# Rapide64a.net
KiCad netlist of a schematic drawn in EAGLE
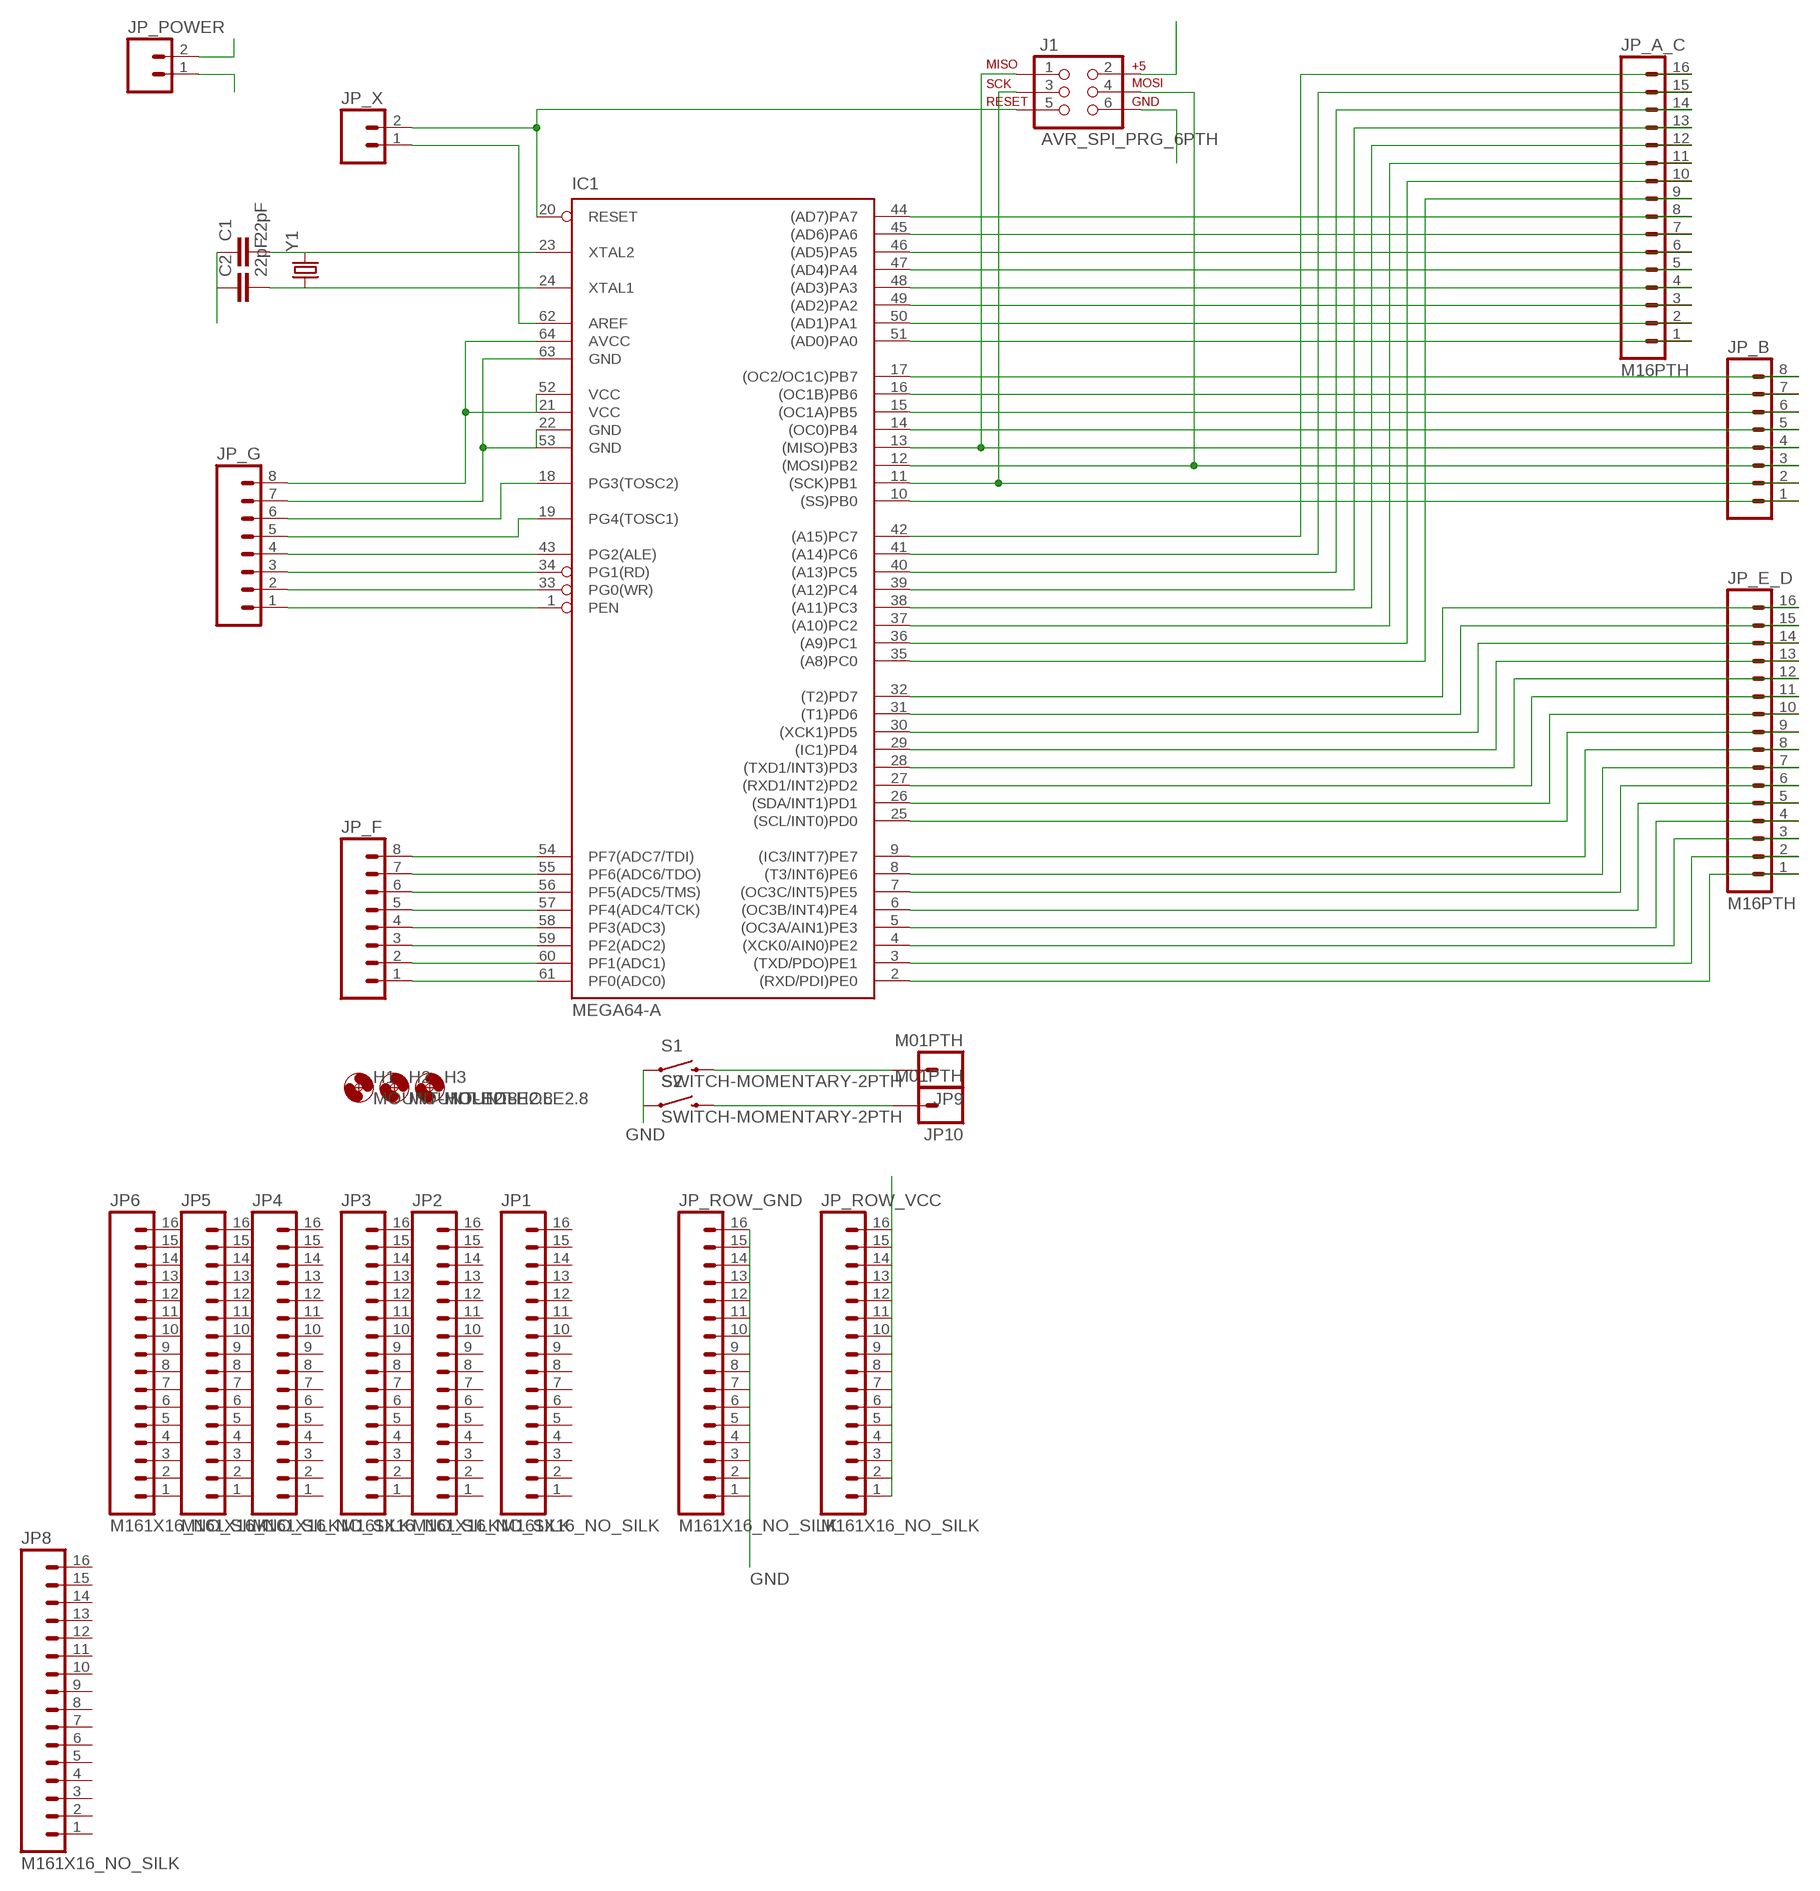
[diagram p0: schematic, sheet 1]

(export (version "E")
  (design (tool "Eeschema 10.0.6"))
  (components
    (comp (ref "C1")
      (value "22pF")
      (footprint "eagle-import:C025-024X044")
      (libsource (lib "eagle-import") (part "C-EU025-024X044"))
    )
    (comp (ref "C2")
      (value "22pF")
      (footprint "eagle-import:C025-024X044")
      (libsource (lib "eagle-import") (part "C-EU025-024X044"))
    )
    (comp (ref "H1")
      (value "MOUNT-HOLE2.8")
      (footprint "eagle-import:2,8")
      (libsource (lib "eagle-import") (part "MOUNT-HOLE2.8"))
    )
    (comp (ref "H2")
      (value "MOUNT-HOLE2.8")
      (footprint "eagle-import:2,8")
      (libsource (lib "eagle-import") (part "MOUNT-HOLE2.8"))
    )
    (comp (ref "H3")
      (value "MOUNT-HOLE2.8")
      (footprint "eagle-import:2,8")
      (libsource (lib "eagle-import") (part "MOUNT-HOLE2.8"))
    )
    (comp (ref "IC1")
      (value "MEGA64-A")
      (footprint "eagle-import:TQFP64")
      (fields (field (name "MPN") "ATMEGA64-16AU"))
      (libsource (lib "eagle-import") (part "MEGA64-A"))
    )
    (comp (ref "J1")
      (value "AVR_SPI_PRG_6PTH")
      (footprint "eagle-import:2X3")
      (libsource (lib "eagle-import") (part "AVR_SPI_PRG_6PTH"))
    )
    (comp (ref "JP1")
      (value "M161X16_NO_SILK")
      (footprint "eagle-import:1X16_NO_SILK")
      (libsource (lib "eagle-import") (part "M161X16_NO_SILK"))
    )
    (comp (ref "JP2")
      (value "M161X16_NO_SILK")
      (footprint "eagle-import:1X16_NO_SILK")
      (libsource (lib "eagle-import") (part "M161X16_NO_SILK"))
    )
    (comp (ref "JP3")
      (value "M161X16_NO_SILK")
      (footprint "eagle-import:1X16_NO_SILK")
      (libsource (lib "eagle-import") (part "M161X16_NO_SILK"))
    )
    (comp (ref "JP4")
      (value "M161X16_NO_SILK")
      (footprint "eagle-import:1X16_NO_SILK")
      (libsource (lib "eagle-import") (part "M161X16_NO_SILK"))
    )
    (comp (ref "JP5")
      (value "M161X16_NO_SILK")
      (footprint "eagle-import:1X16_NO_SILK")
      (libsource (lib "eagle-import") (part "M161X16_NO_SILK"))
    )
    (comp (ref "JP6")
      (value "M161X16_NO_SILK")
      (footprint "eagle-import:1X16_NO_SILK")
      (libsource (lib "eagle-import") (part "M161X16_NO_SILK"))
    )
    (comp (ref "JP8")
      (value "M161X16_NO_SILK")
      (footprint "eagle-import:1X16_NO_SILK")
      (libsource (lib "eagle-import") (part "M161X16_NO_SILK"))
    )
    (comp (ref "JP9")
      (value "M01PTH")
      (footprint "eagle-import:1X01")
      (libsource (lib "eagle-import") (part "M01PTH"))
    )
    (comp (ref "JP10")
      (value "M01PTH")
      (footprint "eagle-import:1X01")
      (libsource (lib "eagle-import") (part "M01PTH"))
    )
    (comp (ref "JP_A_C")
      (value "M16PTH")
      (footprint "eagle-import:1X16")
      (libsource (lib "eagle-import") (part "M16PTH"))
    )
    (comp (ref "JP_B")
      (value "M081X08")
      (footprint "eagle-import:1X08")
      (libsource (lib "eagle-import") (part "M081X08"))
    )
    (comp (ref "JP_E_D")
      (value "M16PTH")
      (footprint "eagle-import:1X16")
      (libsource (lib "eagle-import") (part "M16PTH"))
    )
    (comp (ref "JP_F")
      (value "M081X08")
      (footprint "eagle-import:1X08")
      (libsource (lib "eagle-import") (part "M081X08"))
    )
    (comp (ref "JP_G")
      (value "M081X08")
      (footprint "eagle-import:1X08")
      (libsource (lib "eagle-import") (part "M081X08"))
    )
    (comp (ref "JP_POWER")
      (value "M02PTH")
      (footprint "eagle-import:1X02")
      (libsource (lib "eagle-import") (part "M02PTH"))
    )
    (comp (ref "JP_ROW_GND")
      (value "M161X16_NO_SILK")
      (footprint "eagle-import:1X16_NO_SILK")
      (libsource (lib "eagle-import") (part "M161X16_NO_SILK"))
    )
    (comp (ref "JP_ROW_VCC")
      (value "M161X16_NO_SILK")
      (footprint "eagle-import:1X16_NO_SILK")
      (libsource (lib "eagle-import") (part "M161X16_NO_SILK"))
    )
    (comp (ref "JP_X")
      (value "M02PTH")
      (footprint "eagle-import:1X02")
      (libsource (lib "eagle-import") (part "M02PTH"))
    )
    (comp (ref "S1")
      (value "SWITCH-MOMENTARY-2PTH")
      (footprint "eagle-import:TACTILE-PTH")
      (libsource (lib "eagle-import") (part "SWITCH-MOMENTARY-2PTH"))
    )
    (comp (ref "S2")
      (value "SWITCH-MOMENTARY-2PTH")
      (footprint "eagle-import:TACTILE-PTH")
      (libsource (lib "eagle-import") (part "SWITCH-MOMENTARY-2PTH"))
    )
    (comp (ref "Y1")
      (value "CRYSTALHC49UV")
      (footprint "eagle-import:HC49U-V")
      (libsource (lib "eagle-import") (part "CRYSTALHC49UV"))
    )
  )
  (nets
    (net (code "1") (name "/GND") (class "Default")
      (node (ref "C1") (pin "1") (pinfunction "1_1") (pintype "passive"))
      (node (ref "C2") (pin "1") (pinfunction "1_1") (pintype "passive"))
      (node (ref "IC1") (pin "22") (pinfunction "GND_22") (pintype "power_in"))
      (node (ref "IC1") (pin "53") (pinfunction "GND_53") (pintype "power_in"))
      (node (ref "IC1") (pin "63") (pinfunction "GND_63") (pintype "power_in"))
      (node (ref "J1") (pin "6") (pinfunction "6_6") (pintype "passive"))
      (node (ref "JP_G") (pin "7") (pinfunction "7_7") (pintype "passive"))
      (node (ref "JP_POWER") (pin "1") (pinfunction "1_1") (pintype "passive"))
      (node (ref "JP_ROW_GND") (pin "1") (pinfunction "1_1") (pintype "passive"))
      (node (ref "JP_ROW_GND") (pin "10") (pinfunction "10_10") (pintype "passive"))
      (node (ref "JP_ROW_GND") (pin "11") (pinfunction "11_11") (pintype "passive"))
      (node (ref "JP_ROW_GND") (pin "12") (pinfunction "12_12") (pintype "passive"))
      (node (ref "JP_ROW_GND") (pin "13") (pinfunction "13_13") (pintype "passive"))
      (node (ref "JP_ROW_GND") (pin "14") (pinfunction "14_14") (pintype "passive"))
      (node (ref "JP_ROW_GND") (pin "15") (pinfunction "15_15") (pintype "passive"))
      (node (ref "JP_ROW_GND") (pin "16") (pinfunction "16_16") (pintype "passive"))
      (node (ref "JP_ROW_GND") (pin "2") (pinfunction "2_2") (pintype "passive"))
      (node (ref "JP_ROW_GND") (pin "3") (pinfunction "3_3") (pintype "passive"))
      (node (ref "JP_ROW_GND") (pin "4") (pinfunction "4_4") (pintype "passive"))
      (node (ref "JP_ROW_GND") (pin "5") (pinfunction "5_5") (pintype "passive"))
      (node (ref "JP_ROW_GND") (pin "6") (pinfunction "6_6") (pintype "passive"))
      (node (ref "JP_ROW_GND") (pin "7") (pinfunction "7_7") (pintype "passive"))
      (node (ref "JP_ROW_GND") (pin "8") (pinfunction "8_8") (pintype "passive"))
      (node (ref "JP_ROW_GND") (pin "9") (pinfunction "9_9") (pintype "passive"))
      (node (ref "S1") (pin "1") (pinfunction "1_1") (pintype "passive"))
      (node (ref "S2") (pin "1") (pinfunction "1_1") (pintype "passive"))
    )
    (net (code "2") (name "/VCC") (class "Default")
      (node (ref "IC1") (pin "21") (pinfunction "VCC_21") (pintype "power_in"))
      (node (ref "IC1") (pin "52") (pinfunction "VCC_52") (pintype "power_in"))
      (node (ref "IC1") (pin "64") (pinfunction "AVCC_64") (pintype "power_in"))
      (node (ref "J1") (pin "2") (pinfunction "2_2") (pintype "passive"))
      (node (ref "JP_G") (pin "8") (pinfunction "8_8") (pintype "passive"))
      (node (ref "JP_POWER") (pin "2") (pinfunction "2_2") (pintype "passive"))
      (node (ref "JP_ROW_VCC") (pin "1") (pinfunction "1_1") (pintype "passive"))
      (node (ref "JP_ROW_VCC") (pin "10") (pinfunction "10_10") (pintype "passive"))
      (node (ref "JP_ROW_VCC") (pin "11") (pinfunction "11_11") (pintype "passive"))
      (node (ref "JP_ROW_VCC") (pin "12") (pinfunction "12_12") (pintype "passive"))
      (node (ref "JP_ROW_VCC") (pin "13") (pinfunction "13_13") (pintype "passive"))
      (node (ref "JP_ROW_VCC") (pin "14") (pinfunction "14_14") (pintype "passive"))
      (node (ref "JP_ROW_VCC") (pin "15") (pinfunction "15_15") (pintype "passive"))
      (node (ref "JP_ROW_VCC") (pin "16") (pinfunction "16_16") (pintype "passive"))
      (node (ref "JP_ROW_VCC") (pin "2") (pinfunction "2_2") (pintype "passive"))
      (node (ref "JP_ROW_VCC") (pin "3") (pinfunction "3_3") (pintype "passive"))
      (node (ref "JP_ROW_VCC") (pin "4") (pinfunction "4_4") (pintype "passive"))
      (node (ref "JP_ROW_VCC") (pin "5") (pinfunction "5_5") (pintype "passive"))
      (node (ref "JP_ROW_VCC") (pin "6") (pinfunction "6_6") (pintype "passive"))
      (node (ref "JP_ROW_VCC") (pin "7") (pinfunction "7_7") (pintype "passive"))
      (node (ref "JP_ROW_VCC") (pin "8") (pinfunction "8_8") (pintype "passive"))
      (node (ref "JP_ROW_VCC") (pin "9") (pinfunction "9_9") (pintype "passive"))
    )
    (net (code "3") (name "Net-(IC1-(A8)PC0)") (class "Default")
      (node (ref "IC1") (pin "35") (pinfunction "(A8)PC0_35") (pintype "output"))
      (node (ref "JP_A_C") (pin "9") (pinfunction "9_9") (pintype "passive"))
    )
    (net (code "4") (name "Net-(IC1-(A9)PC1)") (class "Default")
      (node (ref "IC1") (pin "36") (pinfunction "(A9)PC1_36") (pintype "output"))
      (node (ref "JP_A_C") (pin "10") (pinfunction "10_10") (pintype "passive"))
    )
    (net (code "5") (name "Net-(IC1-(A10)PC2)") (class "Default")
      (node (ref "IC1") (pin "37") (pinfunction "(A10)PC2_37") (pintype "output"))
      (node (ref "JP_A_C") (pin "11") (pinfunction "11_11") (pintype "passive"))
    )
    (net (code "6") (name "Net-(IC1-(A11)PC3)") (class "Default")
      (node (ref "IC1") (pin "38") (pinfunction "(A11)PC3_38") (pintype "output"))
      (node (ref "JP_A_C") (pin "12") (pinfunction "12_12") (pintype "passive"))
    )
    (net (code "7") (name "Net-(IC1-(A12)PC4)") (class "Default")
      (node (ref "IC1") (pin "39") (pinfunction "(A12)PC4_39") (pintype "output"))
      (node (ref "JP_A_C") (pin "13") (pinfunction "13_13") (pintype "passive"))
    )
    (net (code "8") (name "Net-(IC1-(A13)PC5)") (class "Default")
      (node (ref "IC1") (pin "40") (pinfunction "(A13)PC5_40") (pintype "output"))
      (node (ref "JP_A_C") (pin "14") (pinfunction "14_14") (pintype "passive"))
    )
    (net (code "9") (name "Net-(IC1-(A14)PC6)") (class "Default")
      (node (ref "IC1") (pin "41") (pinfunction "(A14)PC6_41") (pintype "output"))
      (node (ref "JP_A_C") (pin "15") (pinfunction "15_15") (pintype "passive"))
    )
    (net (code "10") (name "Net-(IC1-(A15)PC7)") (class "Default")
      (node (ref "IC1") (pin "42") (pinfunction "(A15)PC7_42") (pintype "output"))
      (node (ref "JP_A_C") (pin "16") (pinfunction "16_16") (pintype "passive"))
    )
    (net (code "11") (name "Net-(IC1-(AD0)PA0)") (class "Default")
      (node (ref "IC1") (pin "51") (pinfunction "(AD0)PA0_51") (pintype "bidirectional"))
      (node (ref "JP_A_C") (pin "1") (pinfunction "1_1") (pintype "passive"))
    )
    (net (code "12") (name "Net-(IC1-(AD1)PA1)") (class "Default")
      (node (ref "IC1") (pin "50") (pinfunction "(AD1)PA1_50") (pintype "bidirectional"))
      (node (ref "JP_A_C") (pin "2") (pinfunction "2_2") (pintype "passive"))
    )
    (net (code "13") (name "Net-(IC1-(AD2)PA2)") (class "Default")
      (node (ref "IC1") (pin "49") (pinfunction "(AD2)PA2_49") (pintype "bidirectional"))
      (node (ref "JP_A_C") (pin "3") (pinfunction "3_3") (pintype "passive"))
    )
    (net (code "14") (name "Net-(IC1-(AD3)PA3)") (class "Default")
      (node (ref "IC1") (pin "48") (pinfunction "(AD3)PA3_48") (pintype "bidirectional"))
      (node (ref "JP_A_C") (pin "4") (pinfunction "4_4") (pintype "passive"))
    )
    (net (code "15") (name "Net-(IC1-(AD4)PA4)") (class "Default")
      (node (ref "IC1") (pin "47") (pinfunction "(AD4)PA4_47") (pintype "bidirectional"))
      (node (ref "JP_A_C") (pin "5") (pinfunction "5_5") (pintype "passive"))
    )
    (net (code "16") (name "Net-(IC1-(AD5)PA5)") (class "Default")
      (node (ref "IC1") (pin "46") (pinfunction "(AD5)PA5_46") (pintype "bidirectional"))
      (node (ref "JP_A_C") (pin "6") (pinfunction "6_6") (pintype "passive"))
    )
    (net (code "17") (name "Net-(IC1-(AD6)PA6)") (class "Default")
      (node (ref "IC1") (pin "45") (pinfunction "(AD6)PA6_45") (pintype "bidirectional"))
      (node (ref "JP_A_C") (pin "7") (pinfunction "7_7") (pintype "passive"))
    )
    (net (code "18") (name "Net-(IC1-(AD7)PA7)") (class "Default")
      (node (ref "IC1") (pin "44") (pinfunction "(AD7)PA7_44") (pintype "bidirectional"))
      (node (ref "JP_A_C") (pin "8") (pinfunction "8_8") (pintype "passive"))
    )
    (net (code "19") (name "Net-(IC1-(IC1)PD4)") (class "Default")
      (node (ref "IC1") (pin "29") (pinfunction "(IC1)PD4_29") (pintype "bidirectional"))
      (node (ref "JP_E_D") (pin "13") (pinfunction "13_13") (pintype "passive"))
    )
    (net (code "20") (name "Net-(IC1-(IC3{slash}INT7)PE7)") (class "Default")
      (node (ref "IC1") (pin "9") (pinfunction "(IC3/INT7)PE7_9") (pintype "bidirectional"))
      (node (ref "JP_E_D") (pin "8") (pinfunction "8_8") (pintype "passive"))
    )
    (net (code "21") (name "Net-(IC1-(MISO)PB3)") (class "Default")
      (node (ref "IC1") (pin "13") (pinfunction "(MISO)PB3_13") (pintype "bidirectional"))
      (node (ref "J1") (pin "1") (pinfunction "1_1") (pintype "passive"))
      (node (ref "JP_B") (pin "4") (pinfunction "4_4") (pintype "passive"))
    )
    (net (code "22") (name "Net-(IC1-(MOSI)PB2)") (class "Default")
      (node (ref "IC1") (pin "12") (pinfunction "(MOSI)PB2_12") (pintype "bidirectional"))
      (node (ref "J1") (pin "4") (pinfunction "4_4") (pintype "passive"))
      (node (ref "JP_B") (pin "3") (pinfunction "3_3") (pintype "passive"))
    )
    (net (code "23") (name "Net-(IC1-(OC0)PB4)") (class "Default")
      (node (ref "IC1") (pin "14") (pinfunction "(OC0)PB4_14") (pintype "bidirectional"))
      (node (ref "JP_B") (pin "5") (pinfunction "5_5") (pintype "passive"))
    )
    (net (code "24") (name "Net-(IC1-(OC1A)PB5)") (class "Default")
      (node (ref "IC1") (pin "15") (pinfunction "(OC1A)PB5_15") (pintype "bidirectional"))
      (node (ref "JP_B") (pin "6") (pinfunction "6_6") (pintype "passive"))
    )
    (net (code "25") (name "Net-(IC1-(OC1B)PB6)") (class "Default")
      (node (ref "IC1") (pin "16") (pinfunction "(OC1B)PB6_16") (pintype "bidirectional"))
      (node (ref "JP_B") (pin "7") (pinfunction "7_7") (pintype "passive"))
    )
    (net (code "26") (name "Net-(IC1-(OC2{slash}OC1C)PB7)") (class "Default")
      (node (ref "IC1") (pin "17") (pinfunction "(OC2/OC1C)PB7_17") (pintype "bidirectional"))
      (node (ref "JP_B") (pin "8") (pinfunction "8_8") (pintype "passive"))
    )
    (net (code "27") (name "Net-(IC1-(OC3A{slash}AIN1)PE3)") (class "Default")
      (node (ref "IC1") (pin "5") (pinfunction "(OC3A/AIN1)PE3_5") (pintype "bidirectional"))
      (node (ref "JP_E_D") (pin "4") (pinfunction "4_4") (pintype "passive"))
    )
    (net (code "28") (name "Net-(IC1-(OC3B{slash}INT4)PE4)") (class "Default")
      (node (ref "IC1") (pin "6") (pinfunction "(OC3B/INT4)PE4_6") (pintype "bidirectional"))
      (node (ref "JP_E_D") (pin "5") (pinfunction "5_5") (pintype "passive"))
    )
    (net (code "29") (name "Net-(IC1-(OC3C{slash}INT5)PE5)") (class "Default")
      (node (ref "IC1") (pin "7") (pinfunction "(OC3C/INT5)PE5_7") (pintype "bidirectional"))
      (node (ref "JP_E_D") (pin "6") (pinfunction "6_6") (pintype "passive"))
    )
    (net (code "30") (name "Net-(IC1-(RXD1{slash}INT2)PD2)") (class "Default")
      (node (ref "IC1") (pin "27") (pinfunction "(RXD1/INT2)PD2_27") (pintype "bidirectional"))
      (node (ref "JP_E_D") (pin "11") (pinfunction "11_11") (pintype "passive"))
    )
    (net (code "31") (name "Net-(IC1-(RXD{slash}PDI)PE0)") (class "Default")
      (node (ref "IC1") (pin "2") (pinfunction "(RXD/PDI)PE0_2") (pintype "bidirectional"))
      (node (ref "JP_E_D") (pin "1") (pinfunction "1_1") (pintype "passive"))
    )
    (net (code "32") (name "Net-(IC1-(SCK)PB1)") (class "Default")
      (node (ref "IC1") (pin "11") (pinfunction "(SCK)PB1_11") (pintype "bidirectional"))
      (node (ref "J1") (pin "3") (pinfunction "3_3") (pintype "passive"))
      (node (ref "JP_B") (pin "2") (pinfunction "2_2") (pintype "passive"))
    )
    (net (code "33") (name "Net-(IC1-(SCL{slash}INT0)PD0)") (class "Default")
      (node (ref "IC1") (pin "25") (pinfunction "(SCL/INT0)PD0_25") (pintype "bidirectional"))
      (node (ref "JP_E_D") (pin "9") (pinfunction "9_9") (pintype "passive"))
    )
    (net (code "34") (name "Net-(IC1-(SDA{slash}INT1)PD1)") (class "Default")
      (node (ref "IC1") (pin "26") (pinfunction "(SDA/INT1)PD1_26") (pintype "bidirectional"))
      (node (ref "JP_E_D") (pin "10") (pinfunction "10_10") (pintype "passive"))
    )
    (net (code "35") (name "Net-(IC1-(SS)PB0)") (class "Default")
      (node (ref "IC1") (pin "10") (pinfunction "(SS)PB0_10") (pintype "bidirectional"))
      (node (ref "JP_B") (pin "1") (pinfunction "1_1") (pintype "passive"))
    )
    (net (code "36") (name "Net-(IC1-(T1)PD6)") (class "Default")
      (node (ref "IC1") (pin "31") (pinfunction "(T1)PD6_31") (pintype "bidirectional"))
      (node (ref "JP_E_D") (pin "15") (pinfunction "15_15") (pintype "passive"))
    )
    (net (code "37") (name "Net-(IC1-(T2)PD7)") (class "Default")
      (node (ref "IC1") (pin "32") (pinfunction "(T2)PD7_32") (pintype "bidirectional"))
      (node (ref "JP_E_D") (pin "16") (pinfunction "16_16") (pintype "passive"))
    )
    (net (code "38") (name "Net-(IC1-(T3{slash}INT6)PE6)") (class "Default")
      (node (ref "IC1") (pin "8") (pinfunction "(T3/INT6)PE6_8") (pintype "bidirectional"))
      (node (ref "JP_E_D") (pin "7") (pinfunction "7_7") (pintype "passive"))
    )
    (net (code "39") (name "Net-(IC1-(TXD1{slash}INT3)PD3)") (class "Default")
      (node (ref "IC1") (pin "28") (pinfunction "(TXD1/INT3)PD3_28") (pintype "bidirectional"))
      (node (ref "JP_E_D") (pin "12") (pinfunction "12_12") (pintype "passive"))
    )
    (net (code "40") (name "Net-(IC1-(TXD{slash}PDO)PE1)") (class "Default")
      (node (ref "IC1") (pin "3") (pinfunction "(TXD/PDO)PE1_3") (pintype "bidirectional"))
      (node (ref "JP_E_D") (pin "2") (pinfunction "2_2") (pintype "passive"))
    )
    (net (code "41") (name "Net-(IC1-(XCK0{slash}AIN0)PE2)") (class "Default")
      (node (ref "IC1") (pin "4") (pinfunction "(XCK0/AIN0)PE2_4") (pintype "bidirectional"))
      (node (ref "JP_E_D") (pin "3") (pinfunction "3_3") (pintype "passive"))
    )
    (net (code "42") (name "Net-(IC1-(XCK1)PD5)") (class "Default")
      (node (ref "IC1") (pin "30") (pinfunction "(XCK1)PD5_30") (pintype "bidirectional"))
      (node (ref "JP_E_D") (pin "14") (pinfunction "14_14") (pintype "passive"))
    )
    (net (code "43") (name "Net-(IC1-AREF)") (class "Default")
      (node (ref "IC1") (pin "62") (pinfunction "AREF_62") (pintype "passive"))
      (node (ref "JP_X") (pin "1") (pinfunction "1_1") (pintype "passive"))
    )
    (net (code "44") (name "Net-(IC1-PEN)") (class "Default")
      (node (ref "IC1") (pin "1") (pinfunction "PEN_1") (pintype "input"))
      (node (ref "JP_G") (pin "1") (pinfunction "1_1") (pintype "passive"))
    )
    (net (code "45") (name "Net-(IC1-PF0(ADC0))") (class "Default")
      (node (ref "IC1") (pin "61") (pinfunction "PF0(ADC0)_61") (pintype "input"))
      (node (ref "JP_F") (pin "1") (pinfunction "1_1") (pintype "passive"))
    )
    (net (code "46") (name "Net-(IC1-PF1(ADC1))") (class "Default")
      (node (ref "IC1") (pin "60") (pinfunction "PF1(ADC1)_60") (pintype "input"))
      (node (ref "JP_F") (pin "2") (pinfunction "2_2") (pintype "passive"))
    )
    (net (code "47") (name "Net-(IC1-PF2(ADC2))") (class "Default")
      (node (ref "IC1") (pin "59") (pinfunction "PF2(ADC2)_59") (pintype "input"))
      (node (ref "JP_F") (pin "3") (pinfunction "3_3") (pintype "passive"))
    )
    (net (code "48") (name "Net-(IC1-PF3(ADC3))") (class "Default")
      (node (ref "IC1") (pin "58") (pinfunction "PF3(ADC3)_58") (pintype "input"))
      (node (ref "JP_F") (pin "4") (pinfunction "4_4") (pintype "passive"))
    )
    (net (code "49") (name "Net-(IC1-PF4(ADC4{slash}TCK))") (class "Default")
      (node (ref "IC1") (pin "57") (pinfunction "PF4(ADC4/TCK)_57") (pintype "input"))
      (node (ref "JP_F") (pin "5") (pinfunction "5_5") (pintype "passive"))
    )
    (net (code "50") (name "Net-(IC1-PF5(ADC5{slash}TMS))") (class "Default")
      (node (ref "IC1") (pin "56") (pinfunction "PF5(ADC5/TMS)_56") (pintype "input"))
      (node (ref "JP_F") (pin "6") (pinfunction "6_6") (pintype "passive"))
    )
    (net (code "51") (name "Net-(IC1-PF6(ADC6{slash}TDO))") (class "Default")
      (node (ref "IC1") (pin "55") (pinfunction "PF6(ADC6/TDO)_55") (pintype "input"))
      (node (ref "JP_F") (pin "7") (pinfunction "7_7") (pintype "passive"))
    )
    (net (code "52") (name "Net-(IC1-PF7(ADC7{slash}TDI))") (class "Default")
      (node (ref "IC1") (pin "54") (pinfunction "PF7(ADC7/TDI)_54") (pintype "input"))
      (node (ref "JP_F") (pin "8") (pinfunction "8_8") (pintype "passive"))
    )
    (net (code "53") (name "Net-(IC1-PG0(WR))") (class "Default")
      (node (ref "IC1") (pin "33") (pinfunction "PG0(WR)_33") (pintype "bidirectional"))
      (node (ref "JP_G") (pin "2") (pinfunction "2_2") (pintype "passive"))
    )
    (net (code "54") (name "Net-(IC1-PG1(RD))") (class "Default")
      (node (ref "IC1") (pin "34") (pinfunction "PG1(RD)_34") (pintype "bidirectional"))
      (node (ref "JP_G") (pin "3") (pinfunction "3_3") (pintype "passive"))
    )
    (net (code "55") (name "Net-(IC1-PG2(ALE))") (class "Default")
      (node (ref "IC1") (pin "43") (pinfunction "PG2(ALE)_43") (pintype "bidirectional"))
      (node (ref "JP_G") (pin "4") (pinfunction "4_4") (pintype "passive"))
    )
    (net (code "56") (name "Net-(IC1-PG3(TOSC2))") (class "Default")
      (node (ref "IC1") (pin "18") (pinfunction "PG3(TOSC2)_18") (pintype "bidirectional"))
      (node (ref "JP_G") (pin "6") (pinfunction "6_6") (pintype "passive"))
    )
    (net (code "57") (name "Net-(IC1-PG4(TOSC1))") (class "Default")
      (node (ref "IC1") (pin "19") (pinfunction "PG4(TOSC1)_19") (pintype "bidirectional"))
      (node (ref "JP_G") (pin "5") (pinfunction "5_5") (pintype "passive"))
    )
    (net (code "58") (name "Net-(IC1-RESET)") (class "Default")
      (node (ref "IC1") (pin "20") (pinfunction "RESET_20") (pintype "input"))
      (node (ref "J1") (pin "5") (pinfunction "5_5") (pintype "passive"))
      (node (ref "JP_X") (pin "2") (pinfunction "2_2") (pintype "passive"))
    )
    (net (code "59") (name "Net-(IC1-XTAL1)") (class "Default")
      (node (ref "C2") (pin "2") (pinfunction "2_2") (pintype "passive"))
      (node (ref "IC1") (pin "24") (pinfunction "XTAL1_24") (pintype "bidirectional"))
      (node (ref "Y1") (pin "1") (pinfunction "1_1") (pintype "passive"))
    )
    (net (code "60") (name "Net-(IC1-XTAL2)") (class "Default")
      (node (ref "C1") (pin "2") (pinfunction "2_2") (pintype "passive"))
      (node (ref "IC1") (pin "23") (pinfunction "XTAL2_23") (pintype "bidirectional"))
      (node (ref "Y1") (pin "2") (pinfunction "2_2") (pintype "passive"))
    )
    (net (code "61") (name "Net-(S1-2)") (class "Default")
      (node (ref "JP9") (pin "1") (pinfunction "1_1") (pintype "passive"))
      (node (ref "S1") (pin "3") (pinfunction "2_3") (pintype "passive"))
    )
    (net (code "62") (name "Net-(S2-2)") (class "Default")
      (node (ref "JP10") (pin "1") (pinfunction "1_1") (pintype "passive"))
      (node (ref "S2") (pin "3") (pinfunction "2_3") (pintype "passive"))
    )
    (net (code "63") (name "unconnected-(JP1-Pad1)") (class "Default")
      (node (ref "JP1") (pin "1") (pinfunction "1_1") (pintype "passive"))
    )
    (net (code "64") (name "unconnected-(JP1-Pad2)") (class "Default")
      (node (ref "JP1") (pin "2") (pinfunction "2_2") (pintype "passive"))
    )
    (net (code "65") (name "unconnected-(JP1-Pad3)") (class "Default")
      (node (ref "JP1") (pin "3") (pinfunction "3_3") (pintype "passive"))
    )
    (net (code "66") (name "unconnected-(JP1-Pad4)") (class "Default")
      (node (ref "JP1") (pin "4") (pinfunction "4_4") (pintype "passive"))
    )
    (net (code "67") (name "unconnected-(JP1-Pad5)") (class "Default")
      (node (ref "JP1") (pin "5") (pinfunction "5_5") (pintype "passive"))
    )
    (net (code "68") (name "unconnected-(JP1-Pad6)") (class "Default")
      (node (ref "JP1") (pin "6") (pinfunction "6_6") (pintype "passive"))
    )
    (net (code "69") (name "unconnected-(JP1-Pad7)") (class "Default")
      (node (ref "JP1") (pin "7") (pinfunction "7_7") (pintype "passive"))
    )
    (net (code "70") (name "unconnected-(JP1-Pad8)") (class "Default")
      (node (ref "JP1") (pin "8") (pinfunction "8_8") (pintype "passive"))
    )
    (net (code "71") (name "unconnected-(JP1-Pad9)") (class "Default")
      (node (ref "JP1") (pin "9") (pinfunction "9_9") (pintype "passive"))
    )
    (net (code "72") (name "unconnected-(JP1-Pad10)") (class "Default")
      (node (ref "JP1") (pin "10") (pinfunction "10_10") (pintype "passive"))
    )
    (net (code "73") (name "unconnected-(JP1-Pad11)") (class "Default")
      (node (ref "JP1") (pin "11") (pinfunction "11_11") (pintype "passive"))
    )
    (net (code "74") (name "unconnected-(JP1-Pad12)") (class "Default")
      (node (ref "JP1") (pin "12") (pinfunction "12_12") (pintype "passive"))
    )
    (net (code "75") (name "unconnected-(JP1-Pad13)") (class "Default")
      (node (ref "JP1") (pin "13") (pinfunction "13_13") (pintype "passive"))
    )
    (net (code "76") (name "unconnected-(JP1-Pad14)") (class "Default")
      (node (ref "JP1") (pin "14") (pinfunction "14_14") (pintype "passive"))
    )
    (net (code "77") (name "unconnected-(JP1-Pad15)") (class "Default")
      (node (ref "JP1") (pin "15") (pinfunction "15_15") (pintype "passive"))
    )
    (net (code "78") (name "unconnected-(JP1-Pad16)") (class "Default")
      (node (ref "JP1") (pin "16") (pinfunction "16_16") (pintype "passive"))
    )
    (net (code "79") (name "unconnected-(JP2-Pad1)") (class "Default")
      (node (ref "JP2") (pin "1") (pinfunction "1_1") (pintype "passive"))
    )
    (net (code "80") (name "unconnected-(JP2-Pad2)") (class "Default")
      (node (ref "JP2") (pin "2") (pinfunction "2_2") (pintype "passive"))
    )
    (net (code "81") (name "unconnected-(JP2-Pad3)") (class "Default")
      (node (ref "JP2") (pin "3") (pinfunction "3_3") (pintype "passive"))
    )
    (net (code "82") (name "unconnected-(JP2-Pad4)") (class "Default")
      (node (ref "JP2") (pin "4") (pinfunction "4_4") (pintype "passive"))
    )
    (net (code "83") (name "unconnected-(JP2-Pad5)") (class "Default")
      (node (ref "JP2") (pin "5") (pinfunction "5_5") (pintype "passive"))
    )
    (net (code "84") (name "unconnected-(JP2-Pad6)") (class "Default")
      (node (ref "JP2") (pin "6") (pinfunction "6_6") (pintype "passive"))
    )
    (net (code "85") (name "unconnected-(JP2-Pad7)") (class "Default")
      (node (ref "JP2") (pin "7") (pinfunction "7_7") (pintype "passive"))
    )
    (net (code "86") (name "unconnected-(JP2-Pad8)") (class "Default")
      (node (ref "JP2") (pin "8") (pinfunction "8_8") (pintype "passive"))
    )
    (net (code "87") (name "unconnected-(JP2-Pad9)") (class "Default")
      (node (ref "JP2") (pin "9") (pinfunction "9_9") (pintype "passive"))
    )
    (net (code "88") (name "unconnected-(JP2-Pad10)") (class "Default")
      (node (ref "JP2") (pin "10") (pinfunction "10_10") (pintype "passive"))
    )
    (net (code "89") (name "unconnected-(JP2-Pad11)") (class "Default")
      (node (ref "JP2") (pin "11") (pinfunction "11_11") (pintype "passive"))
    )
    (net (code "90") (name "unconnected-(JP2-Pad12)") (class "Default")
      (node (ref "JP2") (pin "12") (pinfunction "12_12") (pintype "passive"))
    )
    (net (code "91") (name "unconnected-(JP2-Pad13)") (class "Default")
      (node (ref "JP2") (pin "13") (pinfunction "13_13") (pintype "passive"))
    )
    (net (code "92") (name "unconnected-(JP2-Pad14)") (class "Default")
      (node (ref "JP2") (pin "14") (pinfunction "14_14") (pintype "passive"))
    )
    (net (code "93") (name "unconnected-(JP2-Pad15)") (class "Default")
      (node (ref "JP2") (pin "15") (pinfunction "15_15") (pintype "passive"))
    )
    (net (code "94") (name "unconnected-(JP2-Pad16)") (class "Default")
      (node (ref "JP2") (pin "16") (pinfunction "16_16") (pintype "passive"))
    )
    (net (code "95") (name "unconnected-(JP3-Pad1)") (class "Default")
      (node (ref "JP3") (pin "1") (pinfunction "1_1") (pintype "passive"))
    )
    (net (code "96") (name "unconnected-(JP3-Pad2)") (class "Default")
      (node (ref "JP3") (pin "2") (pinfunction "2_2") (pintype "passive"))
    )
    (net (code "97") (name "unconnected-(JP3-Pad3)") (class "Default")
      (node (ref "JP3") (pin "3") (pinfunction "3_3") (pintype "passive"))
    )
    (net (code "98") (name "unconnected-(JP3-Pad4)") (class "Default")
      (node (ref "JP3") (pin "4") (pinfunction "4_4") (pintype "passive"))
    )
    (net (code "99") (name "unconnected-(JP3-Pad5)") (class "Default")
      (node (ref "JP3") (pin "5") (pinfunction "5_5") (pintype "passive"))
    )
    (net (code "100") (name "unconnected-(JP3-Pad6)") (class "Default")
      (node (ref "JP3") (pin "6") (pinfunction "6_6") (pintype "passive"))
    )
    (net (code "101") (name "unconnected-(JP3-Pad7)") (class "Default")
      (node (ref "JP3") (pin "7") (pinfunction "7_7") (pintype "passive"))
    )
    (net (code "102") (name "unconnected-(JP3-Pad8)") (class "Default")
      (node (ref "JP3") (pin "8") (pinfunction "8_8") (pintype "passive"))
    )
    (net (code "103") (name "unconnected-(JP3-Pad9)") (class "Default")
      (node (ref "JP3") (pin "9") (pinfunction "9_9") (pintype "passive"))
    )
    (net (code "104") (name "unconnected-(JP3-Pad10)") (class "Default")
      (node (ref "JP3") (pin "10") (pinfunction "10_10") (pintype "passive"))
    )
    (net (code "105") (name "unconnected-(JP3-Pad11)") (class "Default")
      (node (ref "JP3") (pin "11") (pinfunction "11_11") (pintype "passive"))
    )
    (net (code "106") (name "unconnected-(JP3-Pad12)") (class "Default")
      (node (ref "JP3") (pin "12") (pinfunction "12_12") (pintype "passive"))
    )
    (net (code "107") (name "unconnected-(JP3-Pad13)") (class "Default")
      (node (ref "JP3") (pin "13") (pinfunction "13_13") (pintype "passive"))
    )
    (net (code "108") (name "unconnected-(JP3-Pad14)") (class "Default")
      (node (ref "JP3") (pin "14") (pinfunction "14_14") (pintype "passive"))
    )
    (net (code "109") (name "unconnected-(JP3-Pad15)") (class "Default")
      (node (ref "JP3") (pin "15") (pinfunction "15_15") (pintype "passive"))
    )
    (net (code "110") (name "unconnected-(JP3-Pad16)") (class "Default")
      (node (ref "JP3") (pin "16") (pinfunction "16_16") (pintype "passive"))
    )
    (net (code "111") (name "unconnected-(JP4-Pad1)") (class "Default")
      (node (ref "JP4") (pin "1") (pinfunction "1_1") (pintype "passive"))
    )
    (net (code "112") (name "unconnected-(JP4-Pad2)") (class "Default")
      (node (ref "JP4") (pin "2") (pinfunction "2_2") (pintype "passive"))
    )
    (net (code "113") (name "unconnected-(JP4-Pad3)") (class "Default")
      (node (ref "JP4") (pin "3") (pinfunction "3_3") (pintype "passive"))
    )
    (net (code "114") (name "unconnected-(JP4-Pad4)") (class "Default")
      (node (ref "JP4") (pin "4") (pinfunction "4_4") (pintype "passive"))
    )
    (net (code "115") (name "unconnected-(JP4-Pad5)") (class "Default")
      (node (ref "JP4") (pin "5") (pinfunction "5_5") (pintype "passive"))
    )
    (net (code "116") (name "unconnected-(JP4-Pad6)") (class "Default")
      (node (ref "JP4") (pin "6") (pinfunction "6_6") (pintype "passive"))
    )
    (net (code "117") (name "unconnected-(JP4-Pad7)") (class "Default")
      (node (ref "JP4") (pin "7") (pinfunction "7_7") (pintype "passive"))
    )
    (net (code "118") (name "unconnected-(JP4-Pad8)") (class "Default")
      (node (ref "JP4") (pin "8") (pinfunction "8_8") (pintype "passive"))
    )
    (net (code "119") (name "unconnected-(JP4-Pad9)") (class "Default")
      (node (ref "JP4") (pin "9") (pinfunction "9_9") (pintype "passive"))
    )
    (net (code "120") (name "unconnected-(JP4-Pad10)") (class "Default")
      (node (ref "JP4") (pin "10") (pinfunction "10_10") (pintype "passive"))
    )
    (net (code "121") (name "unconnected-(JP4-Pad11)") (class "Default")
      (node (ref "JP4") (pin "11") (pinfunction "11_11") (pintype "passive"))
    )
    (net (code "122") (name "unconnected-(JP4-Pad12)") (class "Default")
      (node (ref "JP4") (pin "12") (pinfunction "12_12") (pintype "passive"))
    )
    (net (code "123") (name "unconnected-(JP4-Pad13)") (class "Default")
      (node (ref "JP4") (pin "13") (pinfunction "13_13") (pintype "passive"))
    )
    (net (code "124") (name "unconnected-(JP4-Pad14)") (class "Default")
      (node (ref "JP4") (pin "14") (pinfunction "14_14") (pintype "passive"))
    )
    (net (code "125") (name "unconnected-(JP4-Pad15)") (class "Default")
      (node (ref "JP4") (pin "15") (pinfunction "15_15") (pintype "passive"))
    )
    (net (code "126") (name "unconnected-(JP4-Pad16)") (class "Default")
      (node (ref "JP4") (pin "16") (pinfunction "16_16") (pintype "passive"))
    )
    (net (code "127") (name "unconnected-(JP5-Pad1)") (class "Default")
      (node (ref "JP5") (pin "1") (pinfunction "1_1") (pintype "passive"))
    )
    (net (code "128") (name "unconnected-(JP5-Pad2)") (class "Default")
      (node (ref "JP5") (pin "2") (pinfunction "2_2") (pintype "passive"))
    )
    (net (code "129") (name "unconnected-(JP5-Pad3)") (class "Default")
      (node (ref "JP5") (pin "3") (pinfunction "3_3") (pintype "passive"))
    )
    (net (code "130") (name "unconnected-(JP5-Pad4)") (class "Default")
      (node (ref "JP5") (pin "4") (pinfunction "4_4") (pintype "passive"))
    )
    (net (code "131") (name "unconnected-(JP5-Pad5)") (class "Default")
      (node (ref "JP5") (pin "5") (pinfunction "5_5") (pintype "passive"))
    )
    (net (code "132") (name "unconnected-(JP5-Pad6)") (class "Default")
      (node (ref "JP5") (pin "6") (pinfunction "6_6") (pintype "passive"))
    )
    (net (code "133") (name "unconnected-(JP5-Pad7)") (class "Default")
      (node (ref "JP5") (pin "7") (pinfunction "7_7") (pintype "passive"))
    )
    (net (code "134") (name "unconnected-(JP5-Pad8)") (class "Default")
      (node (ref "JP5") (pin "8") (pinfunction "8_8") (pintype "passive"))
    )
    (net (code "135") (name "unconnected-(JP5-Pad9)") (class "Default")
      (node (ref "JP5") (pin "9") (pinfunction "9_9") (pintype "passive"))
    )
    (net (code "136") (name "unconnected-(JP5-Pad10)") (class "Default")
      (node (ref "JP5") (pin "10") (pinfunction "10_10") (pintype "passive"))
    )
    (net (code "137") (name "unconnected-(JP5-Pad11)") (class "Default")
      (node (ref "JP5") (pin "11") (pinfunction "11_11") (pintype "passive"))
    )
    (net (code "138") (name "unconnected-(JP5-Pad12)") (class "Default")
      (node (ref "JP5") (pin "12") (pinfunction "12_12") (pintype "passive"))
    )
    (net (code "139") (name "unconnected-(JP5-Pad13)") (class "Default")
      (node (ref "JP5") (pin "13") (pinfunction "13_13") (pintype "passive"))
    )
    (net (code "140") (name "unconnected-(JP5-Pad14)") (class "Default")
      (node (ref "JP5") (pin "14") (pinfunction "14_14") (pintype "passive"))
    )
    (net (code "141") (name "unconnected-(JP5-Pad15)") (class "Default")
      (node (ref "JP5") (pin "15") (pinfunction "15_15") (pintype "passive"))
    )
    (net (code "142") (name "unconnected-(JP5-Pad16)") (class "Default")
      (node (ref "JP5") (pin "16") (pinfunction "16_16") (pintype "passive"))
    )
    (net (code "143") (name "unconnected-(JP6-Pad1)") (class "Default")
      (node (ref "JP6") (pin "1") (pinfunction "1_1") (pintype "passive"))
    )
    (net (code "144") (name "unconnected-(JP6-Pad2)") (class "Default")
      (node (ref "JP6") (pin "2") (pinfunction "2_2") (pintype "passive"))
    )
    (net (code "145") (name "unconnected-(JP6-Pad3)") (class "Default")
      (node (ref "JP6") (pin "3") (pinfunction "3_3") (pintype "passive"))
    )
    (net (code "146") (name "unconnected-(JP6-Pad4)") (class "Default")
      (node (ref "JP6") (pin "4") (pinfunction "4_4") (pintype "passive"))
    )
    (net (code "147") (name "unconnected-(JP6-Pad5)") (class "Default")
      (node (ref "JP6") (pin "5") (pinfunction "5_5") (pintype "passive"))
    )
    (net (code "148") (name "unconnected-(JP6-Pad6)") (class "Default")
      (node (ref "JP6") (pin "6") (pinfunction "6_6") (pintype "passive"))
    )
    (net (code "149") (name "unconnected-(JP6-Pad7)") (class "Default")
      (node (ref "JP6") (pin "7") (pinfunction "7_7") (pintype "passive"))
    )
    (net (code "150") (name "unconnected-(JP6-Pad8)") (class "Default")
      (node (ref "JP6") (pin "8") (pinfunction "8_8") (pintype "passive"))
    )
    (net (code "151") (name "unconnected-(JP6-Pad9)") (class "Default")
      (node (ref "JP6") (pin "9") (pinfunction "9_9") (pintype "passive"))
    )
    (net (code "152") (name "unconnected-(JP6-Pad10)") (class "Default")
      (node (ref "JP6") (pin "10") (pinfunction "10_10") (pintype "passive"))
    )
    (net (code "153") (name "unconnected-(JP6-Pad11)") (class "Default")
      (node (ref "JP6") (pin "11") (pinfunction "11_11") (pintype "passive"))
    )
    (net (code "154") (name "unconnected-(JP6-Pad12)") (class "Default")
      (node (ref "JP6") (pin "12") (pinfunction "12_12") (pintype "passive"))
    )
    (net (code "155") (name "unconnected-(JP6-Pad13)") (class "Default")
      (node (ref "JP6") (pin "13") (pinfunction "13_13") (pintype "passive"))
    )
    (net (code "156") (name "unconnected-(JP6-Pad14)") (class "Default")
      (node (ref "JP6") (pin "14") (pinfunction "14_14") (pintype "passive"))
    )
    (net (code "157") (name "unconnected-(JP6-Pad15)") (class "Default")
      (node (ref "JP6") (pin "15") (pinfunction "15_15") (pintype "passive"))
    )
    (net (code "158") (name "unconnected-(JP6-Pad16)") (class "Default")
      (node (ref "JP6") (pin "16") (pinfunction "16_16") (pintype "passive"))
    )
    (net (code "159") (name "unconnected-(JP8-Pad1)") (class "Default")
      (node (ref "JP8") (pin "1") (pinfunction "1_1") (pintype "passive"))
    )
    (net (code "160") (name "unconnected-(JP8-Pad2)") (class "Default")
      (node (ref "JP8") (pin "2") (pinfunction "2_2") (pintype "passive"))
    )
    (net (code "161") (name "unconnected-(JP8-Pad3)") (class "Default")
      (node (ref "JP8") (pin "3") (pinfunction "3_3") (pintype "passive"))
    )
    (net (code "162") (name "unconnected-(JP8-Pad4)") (class "Default")
      (node (ref "JP8") (pin "4") (pinfunction "4_4") (pintype "passive"))
    )
    (net (code "163") (name "unconnected-(JP8-Pad5)") (class "Default")
      (node (ref "JP8") (pin "5") (pinfunction "5_5") (pintype "passive"))
    )
    (net (code "164") (name "unconnected-(JP8-Pad6)") (class "Default")
      (node (ref "JP8") (pin "6") (pinfunction "6_6") (pintype "passive"))
    )
    (net (code "165") (name "unconnected-(JP8-Pad7)") (class "Default")
      (node (ref "JP8") (pin "7") (pinfunction "7_7") (pintype "passive"))
    )
    (net (code "166") (name "unconnected-(JP8-Pad8)") (class "Default")
      (node (ref "JP8") (pin "8") (pinfunction "8_8") (pintype "passive"))
    )
    (net (code "167") (name "unconnected-(JP8-Pad9)") (class "Default")
      (node (ref "JP8") (pin "9") (pinfunction "9_9") (pintype "passive"))
    )
    (net (code "168") (name "unconnected-(JP8-Pad10)") (class "Default")
      (node (ref "JP8") (pin "10") (pinfunction "10_10") (pintype "passive"))
    )
    (net (code "169") (name "unconnected-(JP8-Pad11)") (class "Default")
      (node (ref "JP8") (pin "11") (pinfunction "11_11") (pintype "passive"))
    )
    (net (code "170") (name "unconnected-(JP8-Pad12)") (class "Default")
      (node (ref "JP8") (pin "12") (pinfunction "12_12") (pintype "passive"))
    )
    (net (code "171") (name "unconnected-(JP8-Pad13)") (class "Default")
      (node (ref "JP8") (pin "13") (pinfunction "13_13") (pintype "passive"))
    )
    (net (code "172") (name "unconnected-(JP8-Pad14)") (class "Default")
      (node (ref "JP8") (pin "14") (pinfunction "14_14") (pintype "passive"))
    )
    (net (code "173") (name "unconnected-(JP8-Pad15)") (class "Default")
      (node (ref "JP8") (pin "15") (pinfunction "15_15") (pintype "passive"))
    )
    (net (code "174") (name "unconnected-(JP8-Pad16)") (class "Default")
      (node (ref "JP8") (pin "16") (pinfunction "16_16") (pintype "passive"))
    )
  )
)
